# 2_bootleg-1-matrix.net
KiCad netlist of a schematic drawn in Altium Designer
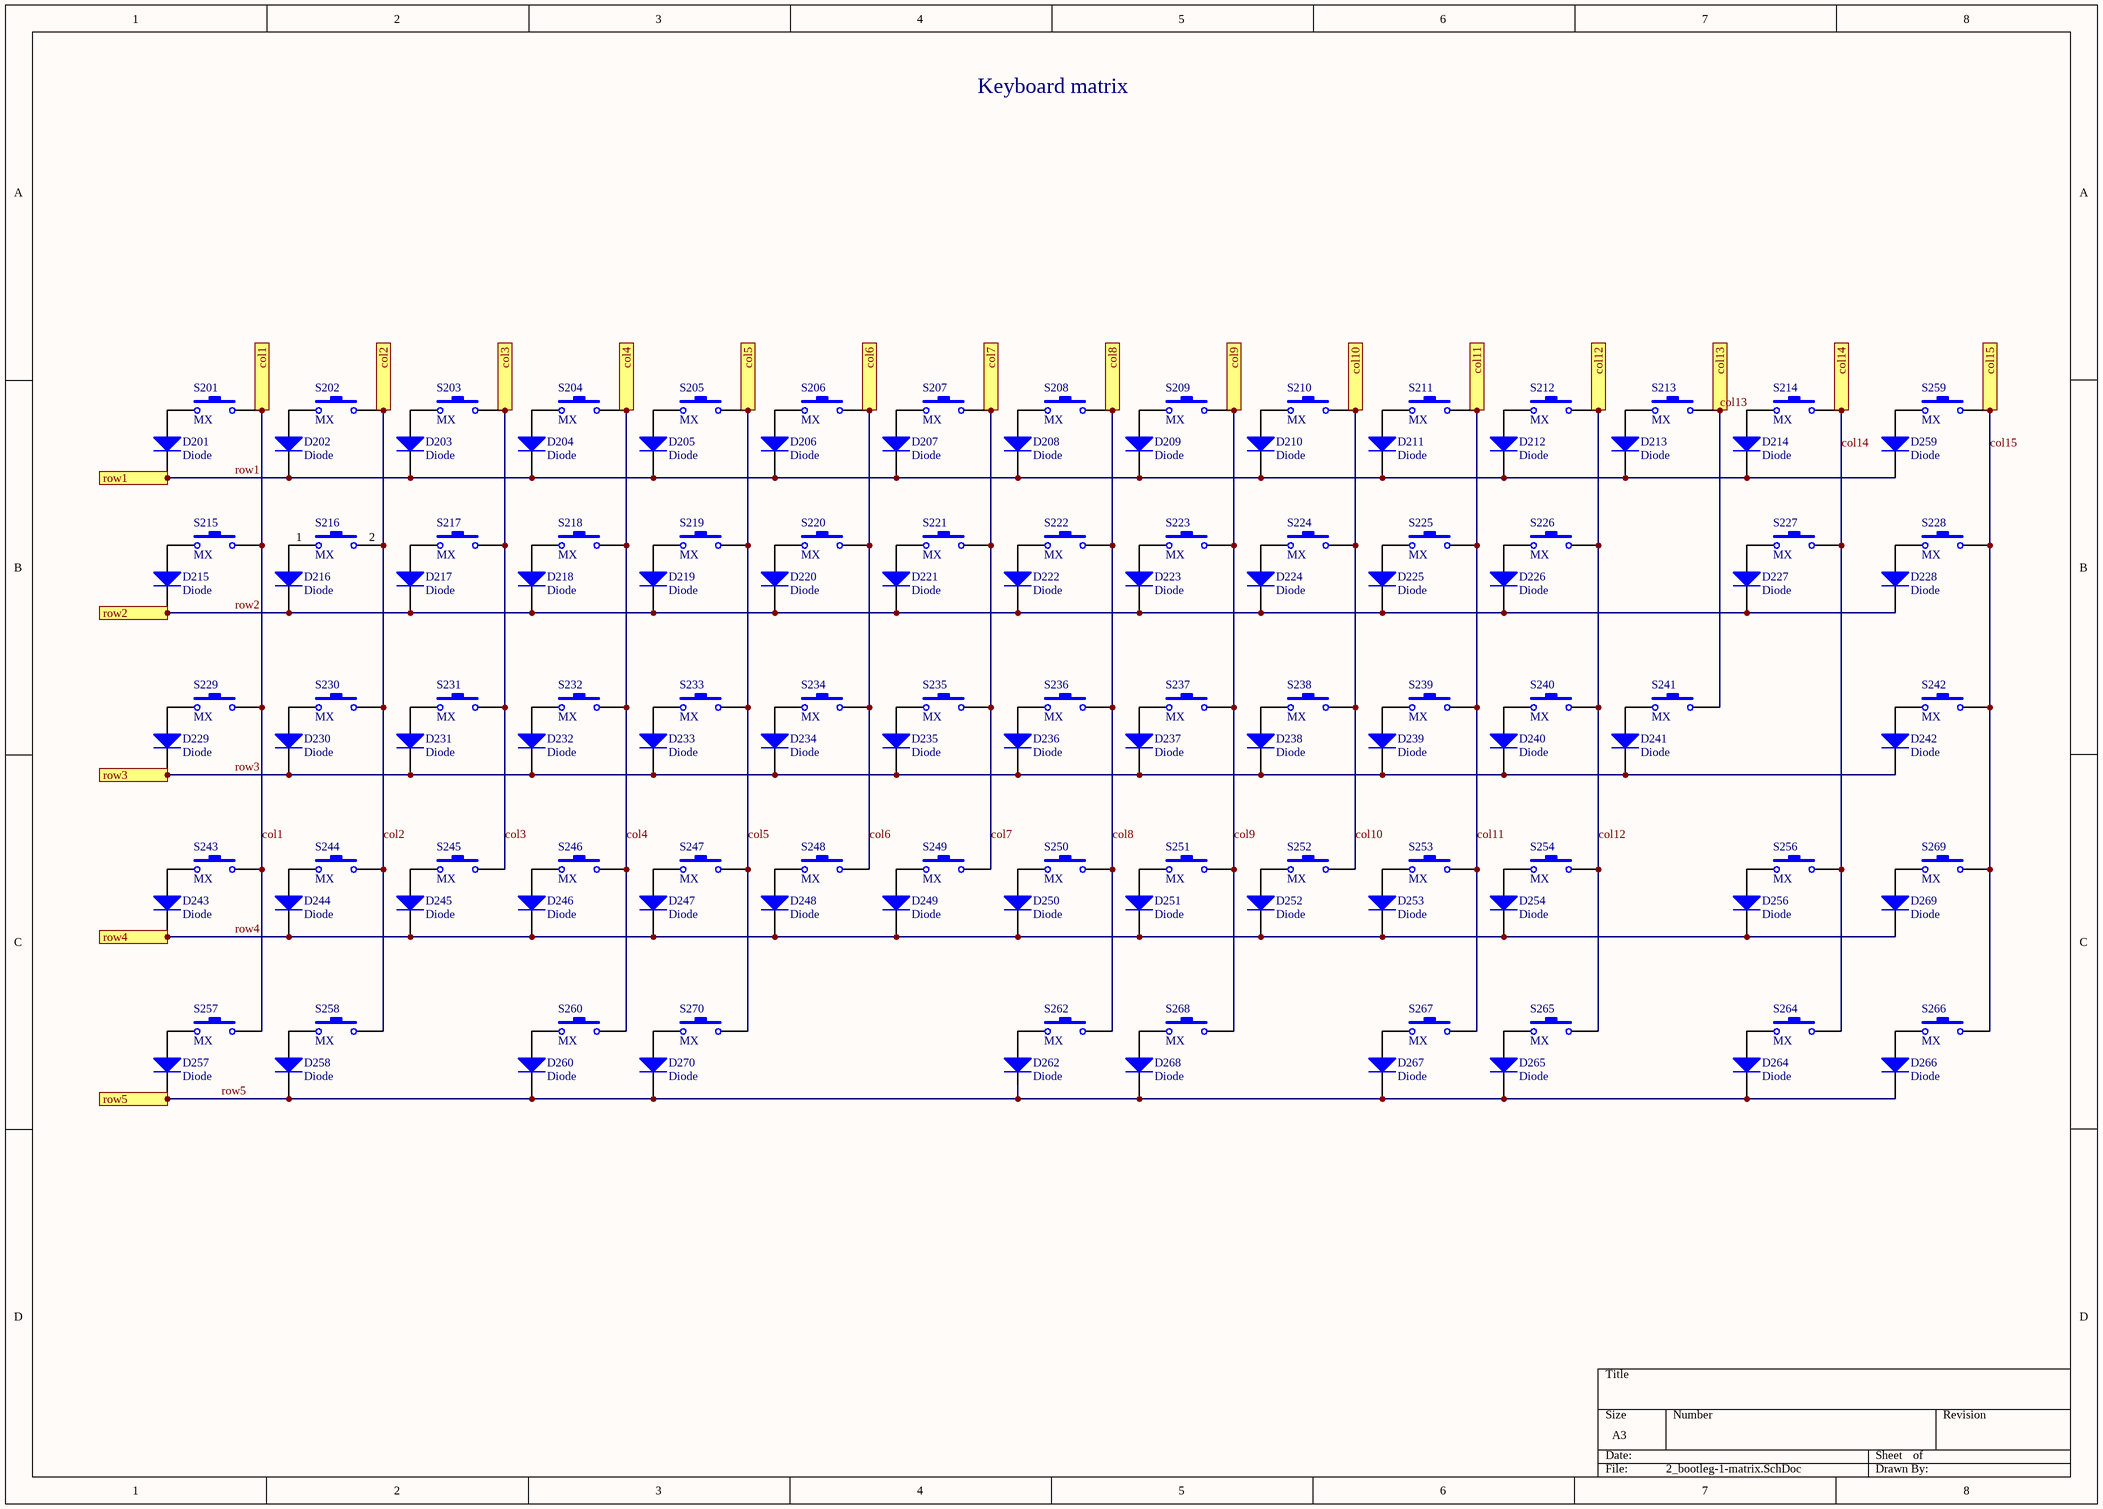
[diagram p0: 2_bootleg-1-matrix.SchDoc]

(export (version "E")
  (design (tool "Eeschema 10.0.6"))
  (components
    (comp (ref "D201")
      (value "Diode")
      (footprint "SOD-123")
      (description "Default Diode")
      (fields (field (name "MFG") "Bourns Inc.") (field (name "LCSC PART #") "C109002"))
      (libsource (lib "Miscellaneous Devices") (part "Diode"))
    )
    (comp (ref "D202")
      (value "Diode")
      (footprint "SOD-123")
      (description "Default Diode")
      (fields (field (name "MFG") "Bourns Inc.") (field (name "LCSC PART #") "C109002"))
      (libsource (lib "Miscellaneous Devices") (part "Diode"))
    )
    (comp (ref "D203")
      (value "Diode")
      (footprint "SOD-123")
      (description "Default Diode")
      (fields (field (name "MFG") "Bourns Inc.") (field (name "LCSC PART #") "C109002"))
      (libsource (lib "Miscellaneous Devices") (part "Diode"))
    )
    (comp (ref "D204")
      (value "Diode")
      (footprint "SOD-123")
      (description "Default Diode")
      (fields (field (name "MFG") "Bourns Inc.") (field (name "LCSC PART #") "C109002"))
      (libsource (lib "Miscellaneous Devices") (part "Diode"))
    )
    (comp (ref "D205")
      (value "Diode")
      (footprint "SOD-123")
      (description "Default Diode")
      (fields (field (name "MFG") "Bourns Inc.") (field (name "LCSC PART #") "C109002"))
      (libsource (lib "Miscellaneous Devices") (part "Diode"))
    )
    (comp (ref "D206")
      (value "Diode")
      (footprint "SOD-123")
      (description "Default Diode")
      (fields (field (name "MFG") "Bourns Inc.") (field (name "LCSC PART #") "C109002"))
      (libsource (lib "Miscellaneous Devices") (part "Diode"))
    )
    (comp (ref "D207")
      (value "Diode")
      (footprint "SOD-123")
      (description "Default Diode")
      (fields (field (name "MFG") "Bourns Inc.") (field (name "LCSC PART #") "C109002"))
      (libsource (lib "Miscellaneous Devices") (part "Diode"))
    )
    (comp (ref "D208")
      (value "Diode")
      (footprint "SOD-123")
      (description "Default Diode")
      (fields (field (name "MFG") "Bourns Inc.") (field (name "LCSC PART #") "C109002"))
      (libsource (lib "Miscellaneous Devices") (part "Diode"))
    )
    (comp (ref "D209")
      (value "Diode")
      (footprint "SOD-123")
      (description "Default Diode")
      (fields (field (name "MFG") "Bourns Inc.") (field (name "LCSC PART #") "C109002"))
      (libsource (lib "Miscellaneous Devices") (part "Diode"))
    )
    (comp (ref "D210")
      (value "Diode")
      (footprint "SOD-123")
      (description "Default Diode")
      (fields (field (name "MFG") "Bourns Inc.") (field (name "LCSC PART #") "C109002"))
      (libsource (lib "Miscellaneous Devices") (part "Diode"))
    )
    (comp (ref "D211")
      (value "Diode")
      (footprint "SOD-123")
      (description "Default Diode")
      (fields (field (name "MFG") "Bourns Inc.") (field (name "LCSC PART #") "C109002"))
      (libsource (lib "Miscellaneous Devices") (part "Diode"))
    )
    (comp (ref "D212")
      (value "Diode")
      (footprint "SOD-123")
      (description "Default Diode")
      (fields (field (name "MFG") "Bourns Inc.") (field (name "LCSC PART #") "C109002"))
      (libsource (lib "Miscellaneous Devices") (part "Diode"))
    )
    (comp (ref "D213")
      (value "Diode")
      (footprint "SOD-123")
      (description "Default Diode")
      (fields (field (name "MFG") "Bourns Inc.") (field (name "LCSC PART #") "C109002"))
      (libsource (lib "Miscellaneous Devices") (part "Diode"))
    )
    (comp (ref "D214")
      (value "Diode")
      (footprint "SOD-123")
      (description "Default Diode")
      (fields (field (name "MFG") "Bourns Inc.") (field (name "LCSC PART #") "C109002"))
      (libsource (lib "Miscellaneous Devices") (part "Diode"))
    )
    (comp (ref "D215")
      (value "Diode")
      (footprint "SOD-123")
      (description "Default Diode")
      (fields (field (name "MFG") "Bourns Inc.") (field (name "LCSC PART #") "C109002"))
      (libsource (lib "Miscellaneous Devices") (part "Diode"))
    )
    (comp (ref "D216")
      (value "Diode")
      (footprint "SOD-123")
      (description "Default Diode")
      (fields (field (name "MFG") "Bourns Inc.") (field (name "LCSC PART #") "C109002"))
      (libsource (lib "Miscellaneous Devices") (part "Diode"))
    )
    (comp (ref "D217")
      (value "Diode")
      (footprint "SOD-123")
      (description "Default Diode")
      (fields (field (name "MFG") "Bourns Inc.") (field (name "LCSC PART #") "C109002"))
      (libsource (lib "Miscellaneous Devices") (part "Diode"))
    )
    (comp (ref "D218")
      (value "Diode")
      (footprint "SOD-123")
      (description "Default Diode")
      (fields (field (name "MFG") "Bourns Inc.") (field (name "LCSC PART #") "C109002"))
      (libsource (lib "Miscellaneous Devices") (part "Diode"))
    )
    (comp (ref "D219")
      (value "Diode")
      (footprint "SOD-123")
      (description "Default Diode")
      (fields (field (name "MFG") "Bourns Inc.") (field (name "LCSC PART #") "C109002"))
      (libsource (lib "Miscellaneous Devices") (part "Diode"))
    )
    (comp (ref "D220")
      (value "Diode")
      (footprint "SOD-123")
      (description "Default Diode")
      (fields (field (name "MFG") "Bourns Inc.") (field (name "LCSC PART #") "C109002"))
      (libsource (lib "Miscellaneous Devices") (part "Diode"))
    )
    (comp (ref "D221")
      (value "Diode")
      (footprint "SOD-123")
      (description "Default Diode")
      (fields (field (name "MFG") "Bourns Inc.") (field (name "LCSC PART #") "C109002"))
      (libsource (lib "Miscellaneous Devices") (part "Diode"))
    )
    (comp (ref "D222")
      (value "Diode")
      (footprint "SOD-123")
      (description "Default Diode")
      (fields (field (name "MFG") "Bourns Inc.") (field (name "LCSC PART #") "C109002"))
      (libsource (lib "Miscellaneous Devices") (part "Diode"))
    )
    (comp (ref "D223")
      (value "Diode")
      (footprint "SOD-123")
      (description "Default Diode")
      (fields (field (name "MFG") "Bourns Inc.") (field (name "LCSC PART #") "C109002"))
      (libsource (lib "Miscellaneous Devices") (part "Diode"))
    )
    (comp (ref "D224")
      (value "Diode")
      (footprint "SOD-123")
      (description "Default Diode")
      (fields (field (name "MFG") "Bourns Inc.") (field (name "LCSC PART #") "C109002"))
      (libsource (lib "Miscellaneous Devices") (part "Diode"))
    )
    (comp (ref "D225")
      (value "Diode")
      (footprint "SOD-123")
      (description "Default Diode")
      (fields (field (name "MFG") "Bourns Inc.") (field (name "LCSC PART #") "C109002"))
      (libsource (lib "Miscellaneous Devices") (part "Diode"))
    )
    (comp (ref "D226")
      (value "Diode")
      (footprint "SOD-123")
      (description "Default Diode")
      (fields (field (name "MFG") "Bourns Inc.") (field (name "LCSC PART #") "C109002"))
      (libsource (lib "Miscellaneous Devices") (part "Diode"))
    )
    (comp (ref "D227")
      (value "Diode")
      (footprint "SOD-123")
      (description "Default Diode")
      (fields (field (name "MFG") "Bourns Inc.") (field (name "LCSC PART #") "C109002"))
      (libsource (lib "Miscellaneous Devices") (part "Diode"))
    )
    (comp (ref "D228")
      (value "Diode")
      (footprint "SOD-123")
      (description "Default Diode")
      (fields (field (name "MFG") "Bourns Inc.") (field (name "LCSC PART #") "C109002"))
      (libsource (lib "Miscellaneous Devices") (part "Diode"))
    )
    (comp (ref "D229")
      (value "Diode")
      (footprint "SOD-123")
      (description "Default Diode")
      (fields (field (name "MFG") "Bourns Inc.") (field (name "LCSC PART #") "C109002"))
      (libsource (lib "Miscellaneous Devices") (part "Diode"))
    )
    (comp (ref "D230")
      (value "Diode")
      (footprint "SOD-123")
      (description "Default Diode")
      (fields (field (name "MFG") "Bourns Inc.") (field (name "LCSC PART #") "C109002"))
      (libsource (lib "Miscellaneous Devices") (part "Diode"))
    )
    (comp (ref "D231")
      (value "Diode")
      (footprint "SOD-123")
      (description "Default Diode")
      (fields (field (name "MFG") "Bourns Inc.") (field (name "LCSC PART #") "C109002"))
      (libsource (lib "Miscellaneous Devices") (part "Diode"))
    )
    (comp (ref "D232")
      (value "Diode")
      (footprint "SOD-123")
      (description "Default Diode")
      (fields (field (name "MFG") "Bourns Inc.") (field (name "LCSC PART #") "C109002"))
      (libsource (lib "Miscellaneous Devices") (part "Diode"))
    )
    (comp (ref "D233")
      (value "Diode")
      (footprint "SOD-123")
      (description "Default Diode")
      (fields (field (name "MFG") "Bourns Inc.") (field (name "LCSC PART #") "C109002"))
      (libsource (lib "Miscellaneous Devices") (part "Diode"))
    )
    (comp (ref "D234")
      (value "Diode")
      (footprint "SOD-123")
      (description "Default Diode")
      (fields (field (name "MFG") "Bourns Inc.") (field (name "LCSC PART #") "C109002"))
      (libsource (lib "Miscellaneous Devices") (part "Diode"))
    )
    (comp (ref "D235")
      (value "Diode")
      (footprint "SOD-123")
      (description "Default Diode")
      (fields (field (name "MFG") "Bourns Inc.") (field (name "LCSC PART #") "C109002"))
      (libsource (lib "Miscellaneous Devices") (part "Diode"))
    )
    (comp (ref "D236")
      (value "Diode")
      (footprint "SOD-123")
      (description "Default Diode")
      (fields (field (name "MFG") "Bourns Inc.") (field (name "LCSC PART #") "C109002"))
      (libsource (lib "Miscellaneous Devices") (part "Diode"))
    )
    (comp (ref "D237")
      (value "Diode")
      (footprint "SOD-123")
      (description "Default Diode")
      (fields (field (name "MFG") "Bourns Inc.") (field (name "LCSC PART #") "C109002"))
      (libsource (lib "Miscellaneous Devices") (part "Diode"))
    )
    (comp (ref "D238")
      (value "Diode")
      (footprint "SOD-123")
      (description "Default Diode")
      (fields (field (name "MFG") "Bourns Inc.") (field (name "LCSC PART #") "C109002"))
      (libsource (lib "Miscellaneous Devices") (part "Diode"))
    )
    (comp (ref "D239")
      (value "Diode")
      (footprint "SOD-123")
      (description "Default Diode")
      (fields (field (name "MFG") "Bourns Inc.") (field (name "LCSC PART #") "C109002"))
      (libsource (lib "Miscellaneous Devices") (part "Diode"))
    )
    (comp (ref "D240")
      (value "Diode")
      (footprint "SOD-123")
      (description "Default Diode")
      (fields (field (name "MFG") "Bourns Inc.") (field (name "LCSC PART #") "C109002"))
      (libsource (lib "Miscellaneous Devices") (part "Diode"))
    )
    (comp (ref "D241")
      (value "Diode")
      (footprint "SOD-123")
      (description "Default Diode")
      (fields (field (name "MFG") "Bourns Inc.") (field (name "LCSC PART #") "C109002"))
      (libsource (lib "Miscellaneous Devices") (part "Diode"))
    )
    (comp (ref "D242")
      (value "Diode")
      (footprint "SOD-123")
      (description "Default Diode")
      (fields (field (name "MFG") "Bourns Inc.") (field (name "LCSC PART #") "C109002"))
      (libsource (lib "Miscellaneous Devices") (part "Diode"))
    )
    (comp (ref "D243")
      (value "Diode")
      (footprint "SOD-123")
      (description "Default Diode")
      (fields (field (name "MFG") "Bourns Inc.") (field (name "LCSC PART #") "C109002"))
      (libsource (lib "Miscellaneous Devices") (part "Diode"))
    )
    (comp (ref "D244")
      (value "Diode")
      (footprint "SOD-123")
      (description "Default Diode")
      (fields (field (name "MFG") "Bourns Inc.") (field (name "LCSC PART #") "C109002"))
      (libsource (lib "Miscellaneous Devices") (part "Diode"))
    )
    (comp (ref "D245")
      (value "Diode")
      (footprint "SOD-123")
      (description "Default Diode")
      (fields (field (name "MFG") "Bourns Inc.") (field (name "LCSC PART #") "C109002"))
      (libsource (lib "Miscellaneous Devices") (part "Diode"))
    )
    (comp (ref "D246")
      (value "Diode")
      (footprint "SOD-123")
      (description "Default Diode")
      (fields (field (name "MFG") "Bourns Inc.") (field (name "LCSC PART #") "C109002"))
      (libsource (lib "Miscellaneous Devices") (part "Diode"))
    )
    (comp (ref "D247")
      (value "Diode")
      (footprint "SOD-123")
      (description "Default Diode")
      (fields (field (name "MFG") "Bourns Inc.") (field (name "LCSC PART #") "C109002"))
      (libsource (lib "Miscellaneous Devices") (part "Diode"))
    )
    (comp (ref "D248")
      (value "Diode")
      (footprint "SOD-123")
      (description "Default Diode")
      (fields (field (name "MFG") "Bourns Inc.") (field (name "LCSC PART #") "C109002"))
      (libsource (lib "Miscellaneous Devices") (part "Diode"))
    )
    (comp (ref "D249")
      (value "Diode")
      (footprint "SOD-123")
      (description "Default Diode")
      (fields (field (name "MFG") "Bourns Inc.") (field (name "LCSC PART #") "C109002"))
      (libsource (lib "Miscellaneous Devices") (part "Diode"))
    )
    (comp (ref "D250")
      (value "Diode")
      (footprint "SOD-123")
      (description "Default Diode")
      (fields (field (name "MFG") "Bourns Inc.") (field (name "LCSC PART #") "C109002"))
      (libsource (lib "Miscellaneous Devices") (part "Diode"))
    )
    (comp (ref "D251")
      (value "Diode")
      (footprint "SOD-123")
      (description "Default Diode")
      (fields (field (name "MFG") "Bourns Inc.") (field (name "LCSC PART #") "C109002"))
      (libsource (lib "Miscellaneous Devices") (part "Diode"))
    )
    (comp (ref "D252")
      (value "Diode")
      (footprint "SOD-123")
      (description "Default Diode")
      (fields (field (name "MFG") "Bourns Inc.") (field (name "LCSC PART #") "C109002"))
      (libsource (lib "Miscellaneous Devices") (part "Diode"))
    )
    (comp (ref "D253")
      (value "Diode")
      (footprint "SOD-123")
      (description "Default Diode")
      (fields (field (name "MFG") "Bourns Inc.") (field (name "LCSC PART #") "C109002"))
      (libsource (lib "Miscellaneous Devices") (part "Diode"))
    )
    (comp (ref "D254")
      (value "Diode")
      (footprint "SOD-123")
      (description "Default Diode")
      (fields (field (name "MFG") "Bourns Inc.") (field (name "LCSC PART #") "C109002"))
      (libsource (lib "Miscellaneous Devices") (part "Diode"))
    )
    (comp (ref "D256")
      (value "Diode")
      (footprint "SOD-123")
      (description "Default Diode")
      (fields (field (name "MFG") "Bourns Inc.") (field (name "LCSC PART #") "C109002"))
      (libsource (lib "Miscellaneous Devices") (part "Diode"))
    )
    (comp (ref "D257")
      (value "Diode")
      (footprint "SOD-123")
      (description "Default Diode")
      (fields (field (name "MFG") "Bourns Inc.") (field (name "LCSC PART #") "C109002"))
      (libsource (lib "Miscellaneous Devices") (part "Diode"))
    )
    (comp (ref "D258")
      (value "Diode")
      (footprint "SOD-123")
      (description "Default Diode")
      (fields (field (name "MFG") "Bourns Inc.") (field (name "LCSC PART #") "C109002"))
      (libsource (lib "Miscellaneous Devices") (part "Diode"))
    )
    (comp (ref "D259")
      (value "Diode")
      (footprint "SOD-123")
      (description "Default Diode")
      (fields (field (name "MFG") "Bourns Inc.") (field (name "LCSC PART #") "C109002"))
      (libsource (lib "Miscellaneous Devices") (part "Diode"))
    )
    (comp (ref "D260")
      (value "Diode")
      (footprint "SOD-123")
      (description "Default Diode")
      (fields (field (name "MFG") "Bourns Inc.") (field (name "LCSC PART #") "C109002"))
      (libsource (lib "Miscellaneous Devices") (part "Diode"))
    )
    (comp (ref "D262")
      (value "Diode")
      (footprint "SOD-123")
      (description "Default Diode")
      (fields (field (name "MFG") "Bourns Inc.") (field (name "LCSC PART #") "C109002"))
      (libsource (lib "Miscellaneous Devices") (part "Diode"))
    )
    (comp (ref "D264")
      (value "Diode")
      (footprint "SOD-123")
      (description "Default Diode")
      (fields (field (name "MFG") "Bourns Inc.") (field (name "LCSC PART #") "C109002"))
      (libsource (lib "Miscellaneous Devices") (part "Diode"))
    )
    (comp (ref "D265")
      (value "Diode")
      (footprint "SOD-123")
      (description "Default Diode")
      (fields (field (name "MFG") "Bourns Inc.") (field (name "LCSC PART #") "C109002"))
      (libsource (lib "Miscellaneous Devices") (part "Diode"))
    )
    (comp (ref "D266")
      (value "Diode")
      (footprint "SOD-123")
      (description "Default Diode")
      (fields (field (name "MFG") "Bourns Inc.") (field (name "LCSC PART #") "C109002"))
      (libsource (lib "Miscellaneous Devices") (part "Diode"))
    )
    (comp (ref "D267")
      (value "Diode")
      (footprint "SOD-123")
      (description "Default Diode")
      (fields (field (name "MFG") "Bourns Inc.") (field (name "LCSC PART #") "C109002"))
      (libsource (lib "Miscellaneous Devices") (part "Diode"))
    )
    (comp (ref "D268")
      (value "Diode")
      (footprint "SOD-123")
      (description "Default Diode")
      (fields (field (name "MFG") "Bourns Inc.") (field (name "LCSC PART #") "C109002"))
      (libsource (lib "Miscellaneous Devices") (part "Diode"))
    )
    (comp (ref "D269")
      (value "Diode")
      (footprint "SOD-123")
      (description "Default Diode")
      (fields (field (name "MFG") "Bourns Inc.") (field (name "LCSC PART #") "C109002"))
      (libsource (lib "Miscellaneous Devices") (part "Diode"))
    )
    (comp (ref "D270")
      (value "Diode")
      (footprint "SOD-123")
      (description "Default Diode")
      (fields (field (name "MFG") "Bourns Inc.") (field (name "LCSC PART #") "C109002"))
      (libsource (lib "Miscellaneous Devices") (part "Diode"))
    )
    (comp (ref "S201")
      (value "MX")
      (footprint "MX-switch - switched pol")
      (description "Switch")
      (libsource (lib "Miscellaneous Devices") (part "SW-PB"))
    )
    (comp (ref "S202")
      (value "MX")
      (footprint "MX-switch - switched pol - connector")
      (description "Switch")
      (libsource (lib "Miscellaneous Devices") (part "SW-PB"))
    )
    (comp (ref "S203")
      (value "MX")
      (footprint "MX-switch - switched pol")
      (description "Switch")
      (libsource (lib "Miscellaneous Devices") (part "SW-PB"))
    )
    (comp (ref "S204")
      (value "MX")
      (footprint "MX-switch - switched pol")
      (description "Switch")
      (libsource (lib "Miscellaneous Devices") (part "SW-PB"))
    )
    (comp (ref "S205")
      (value "MX")
      (footprint "MX-switch - switched pol")
      (description "Switch")
      (libsource (lib "Miscellaneous Devices") (part "SW-PB"))
    )
    (comp (ref "S206")
      (value "MX")
      (footprint "MX-switch - switched pol")
      (description "Switch")
      (libsource (lib "Miscellaneous Devices") (part "SW-PB"))
    )
    (comp (ref "S207")
      (value "MX")
      (footprint "MX-switch - switched pol")
      (description "Switch")
      (libsource (lib "Miscellaneous Devices") (part "SW-PB"))
    )
    (comp (ref "S208")
      (value "MX")
      (footprint "MX-switch - switched pol")
      (description "Switch")
      (libsource (lib "Miscellaneous Devices") (part "SW-PB"))
    )
    (comp (ref "S209")
      (value "MX")
      (footprint "MX-switch - switched pol")
      (description "Switch")
      (libsource (lib "Miscellaneous Devices") (part "SW-PB"))
    )
    (comp (ref "S210")
      (value "MX")
      (footprint "MX-switch - switched pol")
      (description "Switch")
      (libsource (lib "Miscellaneous Devices") (part "SW-PB"))
    )
    (comp (ref "S211")
      (value "MX")
      (footprint "MX-switch - switched pol")
      (description "Switch")
      (libsource (lib "Miscellaneous Devices") (part "SW-PB"))
    )
    (comp (ref "S212")
      (value "MX")
      (footprint "MX-switch - switched pol")
      (description "Switch")
      (libsource (lib "Miscellaneous Devices") (part "SW-PB"))
    )
    (comp (ref "S213")
      (value "MX")
      (footprint "MX-switch - switched pol")
      (description "Switch")
      (libsource (lib "Miscellaneous Devices") (part "SW-PB"))
    )
    (comp (ref "S214")
      (value "MX")
      (footprint "MX-switch - switched pol")
      (description "Switch")
      (libsource (lib "Miscellaneous Devices") (part "SW-PB"))
    )
    (comp (ref "S215")
      (value "MX")
      (footprint "MX-switch - 1.5U")
      (description "TAB")
      (libsource (lib "Miscellaneous Devices") (part "SW-PB"))
    )
    (comp (ref "S216")
      (value "MX")
      (footprint "MX-switch - switched pol")
      (description "Switch")
      (libsource (lib "") (part "SW-PB_1"))
    )
    (comp (ref "S217")
      (value "MX")
      (footprint "MX-switch - switched pol")
      (description "Switch")
      (libsource (lib "Miscellaneous Devices") (part "SW-PB"))
    )
    (comp (ref "S218")
      (value "MX")
      (footprint "MX-switch - switched pol")
      (description "Switch")
      (libsource (lib "Miscellaneous Devices") (part "SW-PB"))
    )
    (comp (ref "S219")
      (value "MX")
      (footprint "MX-switch - switched pol")
      (description "Switch")
      (libsource (lib "Miscellaneous Devices") (part "SW-PB"))
    )
    (comp (ref "S220")
      (value "MX")
      (footprint "MX-switch - switched pol")
      (description "Switch")
      (libsource (lib "Miscellaneous Devices") (part "SW-PB"))
    )
    (comp (ref "S221")
      (value "MX")
      (footprint "MX-switch - switched pol")
      (description "Switch")
      (libsource (lib "Miscellaneous Devices") (part "SW-PB"))
    )
    (comp (ref "S222")
      (value "MX")
      (footprint "MX-switch - switched pol")
      (description "Switch")
      (libsource (lib "Miscellaneous Devices") (part "SW-PB"))
    )
    (comp (ref "S223")
      (value "MX")
      (footprint "MX-switch - switched pol")
      (description "Switch")
      (libsource (lib "Miscellaneous Devices") (part "SW-PB"))
    )
    (comp (ref "S224")
      (value "MX")
      (footprint "MX-switch - switched pol")
      (description "Switch")
      (libsource (lib "Miscellaneous Devices") (part "SW-PB"))
    )
    (comp (ref "S225")
      (value "MX")
      (footprint "MX-switch - switched pol")
      (description "Switch")
      (libsource (lib "Miscellaneous Devices") (part "SW-PB"))
    )
    (comp (ref "S226")
      (value "MX")
      (footprint "MX-switch")
      (description "Switch")
      (libsource (lib "Miscellaneous Devices") (part "SW-PB"))
    )
    (comp (ref "S227")
      (value "MX")
      (footprint "MX-switch - switched pol")
      (description "Switch")
      (libsource (lib "Miscellaneous Devices") (part "SW-PB"))
    )
    (comp (ref "S228")
      (value "MX")
      (footprint "MX-switch - 1.5U")
      (description "Switch")
      (libsource (lib "Miscellaneous Devices") (part "SW-PB"))
    )
    (comp (ref "S229")
      (value "MX")
      (footprint "MX-switch - CAPS")
      (description "Switch")
      (libsource (lib "Miscellaneous Devices") (part "SW-PB"))
    )
    (comp (ref "S230")
      (value "MX")
      (footprint "MX-switch - switched pol")
      (description "Switch")
      (libsource (lib "Miscellaneous Devices") (part "SW-PB"))
    )
    (comp (ref "S231")
      (value "MX")
      (footprint "MX-switch - switched pol")
      (description "Switch")
      (libsource (lib "Miscellaneous Devices") (part "SW-PB"))
    )
    (comp (ref "S232")
      (value "MX")
      (footprint "MX-switch - switched pol")
      (description "Switch")
      (libsource (lib "Miscellaneous Devices") (part "SW-PB"))
    )
    (comp (ref "S233")
      (value "MX")
      (footprint "MX-switch - switched pol")
      (description "Switch")
      (libsource (lib "Miscellaneous Devices") (part "SW-PB"))
    )
    (comp (ref "S234")
      (value "MX")
      (footprint "MX-switch - switched pol")
      (description "Switch")
      (libsource (lib "Miscellaneous Devices") (part "SW-PB"))
    )
    (comp (ref "S235")
      (value "MX")
      (footprint "MX-switch - switched pol")
      (description "Switch")
      (libsource (lib "Miscellaneous Devices") (part "SW-PB"))
    )
    (comp (ref "S236")
      (value "MX")
      (footprint "MX-switch - switched pol")
      (description "Switch")
      (libsource (lib "Miscellaneous Devices") (part "SW-PB"))
    )
    (comp (ref "S237")
      (value "MX")
      (footprint "MX-switch - switched pol")
      (description "Switch")
      (libsource (lib "Miscellaneous Devices") (part "SW-PB"))
    )
    (comp (ref "S238")
      (value "MX")
      (footprint "MX-switch - switched pol")
      (description "Switch")
      (libsource (lib "Miscellaneous Devices") (part "SW-PB"))
    )
    (comp (ref "S239")
      (value "MX")
      (footprint "MX-switch")
      (description "Switch")
      (libsource (lib "Miscellaneous Devices") (part "SW-PB"))
    )
    (comp (ref "S240")
      (value "MX")
      (footprint "MX-switch - switched pol")
      (description "Switch")
      (libsource (lib "Miscellaneous Devices") (part "SW-PB"))
    )
    (comp (ref "S241")
      (value "MX")
      (footprint "MX-switch")
      (description "Switch")
      (libsource (lib "Miscellaneous Devices") (part "SW-PB"))
    )
    (comp (ref "S242")
      (value "MX")
      (footprint "MX-switch - Enter")
      (description "Switch")
      (libsource (lib "Miscellaneous Devices") (part "SW-PB"))
    )
    (comp (ref "S243")
      (value "MX")
      (footprint "MX-switch - Left shift")
      (description "Switch")
      (libsource (lib "Miscellaneous Devices") (part "SW-PB"))
    )
    (comp (ref "S244")
      (value "MX")
      (footprint "MX-switch")
      (description "Switch")
      (libsource (lib "Miscellaneous Devices") (part "SW-PB"))
    )
    (comp (ref "S245")
      (value "MX")
      (footprint "MX-switch - switched pol")
      (description "Switch")
      (libsource (lib "Miscellaneous Devices") (part "SW-PB"))
    )
    (comp (ref "S246")
      (value "MX")
      (footprint "MX-switch - switched pol")
      (description "Switch")
      (libsource (lib "Miscellaneous Devices") (part "SW-PB"))
    )
    (comp (ref "S247")
      (value "MX")
      (footprint "MX-switch - switched pol")
      (description "Switch")
      (libsource (lib "Miscellaneous Devices") (part "SW-PB"))
    )
    (comp (ref "S248")
      (value "MX")
      (footprint "MX-switch - switched pol")
      (description "Switch")
      (libsource (lib "Miscellaneous Devices") (part "SW-PB"))
    )
    (comp (ref "S249")
      (value "MX")
      (footprint "MX-switch - switched pol")
      (description "Switch")
      (libsource (lib "Miscellaneous Devices") (part "SW-PB"))
    )
    (comp (ref "S250")
      (value "MX")
      (footprint "MX-switch - switched pol")
      (description "Switch")
      (libsource (lib "Miscellaneous Devices") (part "SW-PB"))
    )
    (comp (ref "S251")
      (value "MX")
      (footprint "MX-switch - switched pol")
      (description "Switch")
      (libsource (lib "Miscellaneous Devices") (part "SW-PB"))
    )
    (comp (ref "S252")
      (value "MX")
      (footprint "MX-switch - switched pol")
      (description "Switch")
      (libsource (lib "Miscellaneous Devices") (part "SW-PB"))
    )
    (comp (ref "S253")
      (value "MX")
      (footprint "MX-switch - switched pol")
      (description "Switch")
      (libsource (lib "Miscellaneous Devices") (part "SW-PB"))
    )
    (comp (ref "S254")
      (value "MX")
      (footprint "MX-switch - switched pol")
      (description "Switch")
      (libsource (lib "Miscellaneous Devices") (part "SW-PB"))
    )
    (comp (ref "S256")
      (value "MX")
      (footprint "MX-switch - right shift")
      (description "Switch")
      (libsource (lib "Miscellaneous Devices") (part "SW-PB"))
    )
    (comp (ref "S257")
      (value "MX")
      (footprint "MX-switch - 1.5u MOD-L")
      (description "Switch")
      (libsource (lib "Miscellaneous Devices") (part "SW-PB"))
    )
    (comp (ref "S258")
      (value "MX")
      (footprint "MX-switch - 1u MOD-L")
      (description "Switch")
      (libsource (lib "Miscellaneous Devices") (part "SW-PB"))
    )
    (comp (ref "S259")
      (value "MX")
      (footprint "MX-switch - backspace")
      (description "Switch")
      (libsource (lib "Miscellaneous Devices") (part "SW-PB"))
    )
    (comp (ref "S260")
      (value "MX")
      (footprint "MX-switch - 1.5u MOD-L")
      (description "Switch")
      (libsource (lib "Miscellaneous Devices") (part "SW-PB"))
    )
    (comp (ref "S262")
      (value "MX")
      (footprint "MX-switch - Space_V3")
      (description "Switch")
      (libsource (lib "Miscellaneous Devices") (part "SW-PB"))
    )
    (comp (ref "S264")
      (value "MX")
      (footprint "MX-switch - 1u MOD-R")
      (description "Switch")
      (libsource (lib "Miscellaneous Devices") (part "SW-PB"))
    )
    (comp (ref "S265")
      (value "MX")
      (footprint "MX-switch - 1.5u MOD-R")
      (description "Switch")
      (libsource (lib "Miscellaneous Devices") (part "SW-PB"))
    )
    (comp (ref "S266")
      (value "MX")
      (footprint "MX-switch - 1.5u MOD-R")
      (description "Switch")
      (libsource (lib "Miscellaneous Devices") (part "SW-PB"))
    )
    (comp (ref "S267")
      (value "MX")
      (footprint "MX-switch")
      (description "Switch")
      (libsource (lib "Miscellaneous Devices") (part "SW-PB"))
    )
    (comp (ref "S268")
      (value "MX")
      (footprint "MX-switch - R split space_V2")
      (description "Switch")
      (libsource (lib "Miscellaneous Devices") (part "SW-PB"))
    )
    (comp (ref "S269")
      (value "MX")
      (footprint "MX-switch")
      (description "Switch")
      (libsource (lib "Miscellaneous Devices") (part "SW-PB"))
    )
    (comp (ref "S270")
      (value "MX")
      (footprint "MX-switch - L split space_V2")
      (description "Switch")
      (libsource (lib "Miscellaneous Devices") (part "SW-PB"))
    )
  )
  (nets
    (net (code "1") (name "/col1") (class "Default")
      (node (ref "S201") (pin "2") (pinfunction "2_2") (pintype "passive"))
      (node (ref "S215") (pin "2") (pinfunction "2_2") (pintype "passive"))
      (node (ref "S229") (pin "2") (pinfunction "2_2") (pintype "passive"))
      (node (ref "S243") (pin "2") (pinfunction "2_2") (pintype "passive"))
      (node (ref "S257") (pin "1") (pinfunction "1_1") (pintype "passive"))
    )
    (net (code "2") (name "/col2") (class "Default")
      (node (ref "S202") (pin "2") (pinfunction "2_2") (pintype "passive"))
      (node (ref "S216") (pin "2") (pinfunction "2_2") (pintype "passive"))
      (node (ref "S230") (pin "2") (pinfunction "2_2") (pintype "passive"))
      (node (ref "S244") (pin "2") (pinfunction "2_2") (pintype "passive"))
      (node (ref "S258") (pin "2") (pinfunction "2_2") (pintype "passive"))
    )
    (net (code "3") (name "/col3") (class "Default")
      (node (ref "S203") (pin "2") (pinfunction "2_2") (pintype "passive"))
      (node (ref "S217") (pin "2") (pinfunction "2_2") (pintype "passive"))
      (node (ref "S231") (pin "2") (pinfunction "2_2") (pintype "passive"))
      (node (ref "S245") (pin "2") (pinfunction "2_2") (pintype "passive"))
    )
    (net (code "4") (name "/col4") (class "Default")
      (node (ref "S204") (pin "2") (pinfunction "2_2") (pintype "passive"))
      (node (ref "S218") (pin "2") (pinfunction "2_2") (pintype "passive"))
      (node (ref "S232") (pin "2") (pinfunction "2_2") (pintype "passive"))
      (node (ref "S246") (pin "2") (pinfunction "2_2") (pintype "passive"))
      (node (ref "S260") (pin "2") (pinfunction "2_2") (pintype "passive"))
    )
    (net (code "5") (name "/col5") (class "Default")
      (node (ref "S205") (pin "2") (pinfunction "2_2") (pintype "passive"))
      (node (ref "S219") (pin "2") (pinfunction "2_2") (pintype "passive"))
      (node (ref "S233") (pin "2") (pinfunction "2_2") (pintype "passive"))
      (node (ref "S247") (pin "2") (pinfunction "2_2") (pintype "passive"))
      (node (ref "S270") (pin "2") (pinfunction "2_2") (pintype "passive"))
    )
    (net (code "6") (name "/col6") (class "Default")
      (node (ref "S206") (pin "2") (pinfunction "2_2") (pintype "passive"))
      (node (ref "S220") (pin "2") (pinfunction "2_2") (pintype "passive"))
      (node (ref "S234") (pin "2") (pinfunction "2_2") (pintype "passive"))
      (node (ref "S248") (pin "2") (pinfunction "2_2") (pintype "passive"))
    )
    (net (code "7") (name "/col7") (class "Default")
      (node (ref "S207") (pin "2") (pinfunction "2_2") (pintype "passive"))
      (node (ref "S221") (pin "2") (pinfunction "2_2") (pintype "passive"))
      (node (ref "S235") (pin "2") (pinfunction "2_2") (pintype "passive"))
      (node (ref "S249") (pin "2") (pinfunction "2_2") (pintype "passive"))
    )
    (net (code "8") (name "/col8") (class "Default")
      (node (ref "S208") (pin "2") (pinfunction "2_2") (pintype "passive"))
      (node (ref "S222") (pin "2") (pinfunction "2_2") (pintype "passive"))
      (node (ref "S236") (pin "2") (pinfunction "2_2") (pintype "passive"))
      (node (ref "S250") (pin "2") (pinfunction "2_2") (pintype "passive"))
      (node (ref "S262") (pin "2") (pinfunction "2_2") (pintype "passive"))
    )
    (net (code "9") (name "/col9") (class "Default")
      (node (ref "S209") (pin "2") (pinfunction "2_2") (pintype "passive"))
      (node (ref "S223") (pin "2") (pinfunction "2_2") (pintype "passive"))
      (node (ref "S237") (pin "2") (pinfunction "2_2") (pintype "passive"))
      (node (ref "S251") (pin "2") (pinfunction "2_2") (pintype "passive"))
      (node (ref "S268") (pin "2") (pinfunction "2_2") (pintype "passive"))
    )
    (net (code "10") (name "/col10") (class "Default")
      (node (ref "S210") (pin "2") (pinfunction "2_2") (pintype "passive"))
      (node (ref "S224") (pin "2") (pinfunction "2_2") (pintype "passive"))
      (node (ref "S238") (pin "2") (pinfunction "2_2") (pintype "passive"))
      (node (ref "S252") (pin "2") (pinfunction "2_2") (pintype "passive"))
    )
    (net (code "11") (name "/col11") (class "Default")
      (node (ref "S211") (pin "2") (pinfunction "2_2") (pintype "passive"))
      (node (ref "S225") (pin "2") (pinfunction "2_2") (pintype "passive"))
      (node (ref "S239") (pin "2") (pinfunction "2_2") (pintype "passive"))
      (node (ref "S253") (pin "2") (pinfunction "2_2") (pintype "passive"))
      (node (ref "S267") (pin "2") (pinfunction "2_2") (pintype "passive"))
    )
    (net (code "12") (name "/col12") (class "Default")
      (node (ref "S212") (pin "2") (pinfunction "2_2") (pintype "passive"))
      (node (ref "S226") (pin "2") (pinfunction "2_2") (pintype "passive"))
      (node (ref "S240") (pin "2") (pinfunction "2_2") (pintype "passive"))
      (node (ref "S254") (pin "2") (pinfunction "2_2") (pintype "passive"))
      (node (ref "S265") (pin "1") (pinfunction "1_1") (pintype "passive"))
    )
    (net (code "13") (name "/col13") (class "Default")
      (node (ref "S213") (pin "2") (pinfunction "2_2") (pintype "passive"))
      (node (ref "S241") (pin "2") (pinfunction "2_2") (pintype "passive"))
    )
    (net (code "14") (name "/col14") (class "Default")
      (node (ref "S214") (pin "2") (pinfunction "2_2") (pintype "passive"))
      (node (ref "S227") (pin "2") (pinfunction "2_2") (pintype "passive"))
      (node (ref "S256") (pin "2") (pinfunction "2_2") (pintype "passive"))
      (node (ref "S264") (pin "2") (pinfunction "2_2") (pintype "passive"))
    )
    (net (code "15") (name "/col15") (class "Default")
      (node (ref "S228") (pin "2") (pinfunction "2_2") (pintype "passive"))
      (node (ref "S242") (pin "2") (pinfunction "2_2") (pintype "passive"))
      (node (ref "S259") (pin "2") (pinfunction "2_2") (pintype "passive"))
      (node (ref "S266") (pin "2") (pinfunction "2_2") (pintype "passive"))
      (node (ref "S269") (pin "2") (pinfunction "2_2") (pintype "passive"))
    )
    (net (code "16") (name "/row1") (class "Default")
      (node (ref "D201") (pin "2") (pinfunction "K_2") (pintype "passive"))
      (node (ref "D202") (pin "2") (pinfunction "K_2") (pintype "passive"))
      (node (ref "D203") (pin "2") (pinfunction "K_2") (pintype "passive"))
      (node (ref "D204") (pin "2") (pinfunction "K_2") (pintype "passive"))
      (node (ref "D205") (pin "2") (pinfunction "K_2") (pintype "passive"))
      (node (ref "D206") (pin "2") (pinfunction "K_2") (pintype "passive"))
      (node (ref "D207") (pin "2") (pinfunction "K_2") (pintype "passive"))
      (node (ref "D208") (pin "2") (pinfunction "K_2") (pintype "passive"))
      (node (ref "D209") (pin "2") (pinfunction "K_2") (pintype "passive"))
      (node (ref "D210") (pin "2") (pinfunction "K_2") (pintype "passive"))
      (node (ref "D211") (pin "2") (pinfunction "K_2") (pintype "passive"))
      (node (ref "D212") (pin "2") (pinfunction "K_2") (pintype "passive"))
      (node (ref "D213") (pin "2") (pinfunction "K_2") (pintype "passive"))
      (node (ref "D214") (pin "2") (pinfunction "K_2") (pintype "passive"))
      (node (ref "D259") (pin "2") (pinfunction "K_2") (pintype "passive"))
    )
    (net (code "17") (name "/row2") (class "Default")
      (node (ref "D215") (pin "2") (pinfunction "K_2") (pintype "passive"))
      (node (ref "D216") (pin "2") (pinfunction "K_2") (pintype "passive"))
      (node (ref "D217") (pin "2") (pinfunction "K_2") (pintype "passive"))
      (node (ref "D218") (pin "2") (pinfunction "K_2") (pintype "passive"))
      (node (ref "D219") (pin "2") (pinfunction "K_2") (pintype "passive"))
      (node (ref "D220") (pin "2") (pinfunction "K_2") (pintype "passive"))
      (node (ref "D221") (pin "2") (pinfunction "K_2") (pintype "passive"))
      (node (ref "D222") (pin "2") (pinfunction "K_2") (pintype "passive"))
      (node (ref "D223") (pin "2") (pinfunction "K_2") (pintype "passive"))
      (node (ref "D224") (pin "2") (pinfunction "K_2") (pintype "passive"))
      (node (ref "D225") (pin "2") (pinfunction "K_2") (pintype "passive"))
      (node (ref "D226") (pin "2") (pinfunction "K_2") (pintype "passive"))
      (node (ref "D227") (pin "2") (pinfunction "K_2") (pintype "passive"))
      (node (ref "D228") (pin "2") (pinfunction "K_2") (pintype "passive"))
    )
    (net (code "18") (name "/row3") (class "Default")
      (node (ref "D229") (pin "2") (pinfunction "K_2") (pintype "passive"))
      (node (ref "D230") (pin "2") (pinfunction "K_2") (pintype "passive"))
      (node (ref "D231") (pin "2") (pinfunction "K_2") (pintype "passive"))
      (node (ref "D232") (pin "2") (pinfunction "K_2") (pintype "passive"))
      (node (ref "D233") (pin "2") (pinfunction "K_2") (pintype "passive"))
      (node (ref "D234") (pin "2") (pinfunction "K_2") (pintype "passive"))
      (node (ref "D235") (pin "2") (pinfunction "K_2") (pintype "passive"))
      (node (ref "D236") (pin "2") (pinfunction "K_2") (pintype "passive"))
      (node (ref "D237") (pin "2") (pinfunction "K_2") (pintype "passive"))
      (node (ref "D238") (pin "2") (pinfunction "K_2") (pintype "passive"))
      (node (ref "D239") (pin "2") (pinfunction "K_2") (pintype "passive"))
      (node (ref "D240") (pin "2") (pinfunction "K_2") (pintype "passive"))
      (node (ref "D241") (pin "2") (pinfunction "K_2") (pintype "passive"))
      (node (ref "D242") (pin "2") (pinfunction "K_2") (pintype "passive"))
    )
    (net (code "19") (name "/row4") (class "Default")
      (node (ref "D243") (pin "2") (pinfunction "K_2") (pintype "passive"))
      (node (ref "D244") (pin "2") (pinfunction "K_2") (pintype "passive"))
      (node (ref "D245") (pin "2") (pinfunction "K_2") (pintype "passive"))
      (node (ref "D246") (pin "2") (pinfunction "K_2") (pintype "passive"))
      (node (ref "D247") (pin "2") (pinfunction "K_2") (pintype "passive"))
      (node (ref "D248") (pin "2") (pinfunction "K_2") (pintype "passive"))
      (node (ref "D249") (pin "2") (pinfunction "K_2") (pintype "passive"))
      (node (ref "D250") (pin "2") (pinfunction "K_2") (pintype "passive"))
      (node (ref "D251") (pin "2") (pinfunction "K_2") (pintype "passive"))
      (node (ref "D252") (pin "2") (pinfunction "K_2") (pintype "passive"))
      (node (ref "D253") (pin "2") (pinfunction "K_2") (pintype "passive"))
      (node (ref "D254") (pin "2") (pinfunction "K_2") (pintype "passive"))
      (node (ref "D256") (pin "2") (pinfunction "K_2") (pintype "passive"))
      (node (ref "D269") (pin "2") (pinfunction "K_2") (pintype "passive"))
    )
    (net (code "20") (name "/row5") (class "Default")
      (node (ref "D257") (pin "2") (pinfunction "K_2") (pintype "passive"))
      (node (ref "D258") (pin "2") (pinfunction "K_2") (pintype "passive"))
      (node (ref "D260") (pin "2") (pinfunction "K_2") (pintype "passive"))
      (node (ref "D262") (pin "2") (pinfunction "K_2") (pintype "passive"))
      (node (ref "D264") (pin "2") (pinfunction "K_2") (pintype "passive"))
      (node (ref "D265") (pin "2") (pinfunction "K_2") (pintype "passive"))
      (node (ref "D266") (pin "2") (pinfunction "K_2") (pintype "passive"))
      (node (ref "D267") (pin "2") (pinfunction "K_2") (pintype "passive"))
      (node (ref "D268") (pin "2") (pinfunction "K_2") (pintype "passive"))
      (node (ref "D270") (pin "2") (pinfunction "K_2") (pintype "passive"))
    )
    (net (code "21") (name "Net-(D201-A)") (class "Default")
      (node (ref "D201") (pin "1") (pinfunction "A_1") (pintype "passive"))
      (node (ref "S201") (pin "1") (pinfunction "1_1") (pintype "passive"))
    )
    (net (code "22") (name "Net-(D202-A)") (class "Default")
      (node (ref "D202") (pin "1") (pinfunction "A_1") (pintype "passive"))
      (node (ref "S202") (pin "1") (pinfunction "1_1") (pintype "passive"))
    )
    (net (code "23") (name "Net-(D203-A)") (class "Default")
      (node (ref "D203") (pin "1") (pinfunction "A_1") (pintype "passive"))
      (node (ref "S203") (pin "1") (pinfunction "1_1") (pintype "passive"))
    )
    (net (code "24") (name "Net-(D204-A)") (class "Default")
      (node (ref "D204") (pin "1") (pinfunction "A_1") (pintype "passive"))
      (node (ref "S204") (pin "1") (pinfunction "1_1") (pintype "passive"))
    )
    (net (code "25") (name "Net-(D205-A)") (class "Default")
      (node (ref "D205") (pin "1") (pinfunction "A_1") (pintype "passive"))
      (node (ref "S205") (pin "1") (pinfunction "1_1") (pintype "passive"))
    )
    (net (code "26") (name "Net-(D206-A)") (class "Default")
      (node (ref "D206") (pin "1") (pinfunction "A_1") (pintype "passive"))
      (node (ref "S206") (pin "1") (pinfunction "1_1") (pintype "passive"))
    )
    (net (code "27") (name "Net-(D207-A)") (class "Default")
      (node (ref "D207") (pin "1") (pinfunction "A_1") (pintype "passive"))
      (node (ref "S207") (pin "1") (pinfunction "1_1") (pintype "passive"))
    )
    (net (code "28") (name "Net-(D208-A)") (class "Default")
      (node (ref "D208") (pin "1") (pinfunction "A_1") (pintype "passive"))
      (node (ref "S208") (pin "1") (pinfunction "1_1") (pintype "passive"))
    )
    (net (code "29") (name "Net-(D209-A)") (class "Default")
      (node (ref "D209") (pin "1") (pinfunction "A_1") (pintype "passive"))
      (node (ref "S209") (pin "1") (pinfunction "1_1") (pintype "passive"))
    )
    (net (code "30") (name "Net-(D210-A)") (class "Default")
      (node (ref "D210") (pin "1") (pinfunction "A_1") (pintype "passive"))
      (node (ref "S210") (pin "1") (pinfunction "1_1") (pintype "passive"))
    )
    (net (code "31") (name "Net-(D211-A)") (class "Default")
      (node (ref "D211") (pin "1") (pinfunction "A_1") (pintype "passive"))
      (node (ref "S211") (pin "1") (pinfunction "1_1") (pintype "passive"))
    )
    (net (code "32") (name "Net-(D212-A)") (class "Default")
      (node (ref "D212") (pin "1") (pinfunction "A_1") (pintype "passive"))
      (node (ref "S212") (pin "1") (pinfunction "1_1") (pintype "passive"))
    )
    (net (code "33") (name "Net-(D213-A)") (class "Default")
      (node (ref "D213") (pin "1") (pinfunction "A_1") (pintype "passive"))
      (node (ref "S213") (pin "1") (pinfunction "1_1") (pintype "passive"))
    )
    (net (code "34") (name "Net-(D214-A)") (class "Default")
      (node (ref "D214") (pin "1") (pinfunction "A_1") (pintype "passive"))
      (node (ref "S214") (pin "1") (pinfunction "1_1") (pintype "passive"))
    )
    (net (code "35") (name "Net-(D215-A)") (class "Default")
      (node (ref "D215") (pin "1") (pinfunction "A_1") (pintype "passive"))
      (node (ref "S215") (pin "1") (pinfunction "1_1") (pintype "passive"))
    )
    (net (code "36") (name "Net-(D216-A)") (class "Default")
      (node (ref "D216") (pin "1") (pinfunction "A_1") (pintype "passive"))
      (node (ref "S216") (pin "1") (pinfunction "1_1") (pintype "passive"))
    )
    (net (code "37") (name "Net-(D217-A)") (class "Default")
      (node (ref "D217") (pin "1") (pinfunction "A_1") (pintype "passive"))
      (node (ref "S217") (pin "1") (pinfunction "1_1") (pintype "passive"))
    )
    (net (code "38") (name "Net-(D218-A)") (class "Default")
      (node (ref "D218") (pin "1") (pinfunction "A_1") (pintype "passive"))
      (node (ref "S218") (pin "1") (pinfunction "1_1") (pintype "passive"))
    )
    (net (code "39") (name "Net-(D219-A)") (class "Default")
      (node (ref "D219") (pin "1") (pinfunction "A_1") (pintype "passive"))
      (node (ref "S219") (pin "1") (pinfunction "1_1") (pintype "passive"))
    )
    (net (code "40") (name "Net-(D220-A)") (class "Default")
      (node (ref "D220") (pin "1") (pinfunction "A_1") (pintype "passive"))
      (node (ref "S220") (pin "1") (pinfunction "1_1") (pintype "passive"))
    )
    (net (code "41") (name "Net-(D221-A)") (class "Default")
      (node (ref "D221") (pin "1") (pinfunction "A_1") (pintype "passive"))
      (node (ref "S221") (pin "1") (pinfunction "1_1") (pintype "passive"))
    )
    (net (code "42") (name "Net-(D222-A)") (class "Default")
      (node (ref "D222") (pin "1") (pinfunction "A_1") (pintype "passive"))
      (node (ref "S222") (pin "1") (pinfunction "1_1") (pintype "passive"))
    )
    (net (code "43") (name "Net-(D223-A)") (class "Default")
      (node (ref "D223") (pin "1") (pinfunction "A_1") (pintype "passive"))
      (node (ref "S223") (pin "1") (pinfunction "1_1") (pintype "passive"))
    )
    (net (code "44") (name "Net-(D224-A)") (class "Default")
      (node (ref "D224") (pin "1") (pinfunction "A_1") (pintype "passive"))
      (node (ref "S224") (pin "1") (pinfunction "1_1") (pintype "passive"))
    )
    (net (code "45") (name "Net-(D225-A)") (class "Default")
      (node (ref "D225") (pin "1") (pinfunction "A_1") (pintype "passive"))
      (node (ref "S225") (pin "1") (pinfunction "1_1") (pintype "passive"))
    )
    (net (code "46") (name "Net-(D226-A)") (class "Default")
      (node (ref "D226") (pin "1") (pinfunction "A_1") (pintype "passive"))
      (node (ref "S226") (pin "1") (pinfunction "1_1") (pintype "passive"))
    )
    (net (code "47") (name "Net-(D227-A)") (class "Default")
      (node (ref "D227") (pin "1") (pinfunction "A_1") (pintype "passive"))
      (node (ref "S227") (pin "1") (pinfunction "1_1") (pintype "passive"))
    )
    (net (code "48") (name "Net-(D228-A)") (class "Default")
      (node (ref "D228") (pin "1") (pinfunction "A_1") (pintype "passive"))
      (node (ref "S228") (pin "1") (pinfunction "1_1") (pintype "passive"))
    )
    (net (code "49") (name "Net-(D229-A)") (class "Default")
      (node (ref "D229") (pin "1") (pinfunction "A_1") (pintype "passive"))
      (node (ref "S229") (pin "1") (pinfunction "1_1") (pintype "passive"))
    )
    (net (code "50") (name "Net-(D230-A)") (class "Default")
      (node (ref "D230") (pin "1") (pinfunction "A_1") (pintype "passive"))
      (node (ref "S230") (pin "1") (pinfunction "1_1") (pintype "passive"))
    )
    (net (code "51") (name "Net-(D231-A)") (class "Default")
      (node (ref "D231") (pin "1") (pinfunction "A_1") (pintype "passive"))
      (node (ref "S231") (pin "1") (pinfunction "1_1") (pintype "passive"))
    )
    (net (code "52") (name "Net-(D232-A)") (class "Default")
      (node (ref "D232") (pin "1") (pinfunction "A_1") (pintype "passive"))
      (node (ref "S232") (pin "1") (pinfunction "1_1") (pintype "passive"))
    )
    (net (code "53") (name "Net-(D233-A)") (class "Default")
      (node (ref "D233") (pin "1") (pinfunction "A_1") (pintype "passive"))
      (node (ref "S233") (pin "1") (pinfunction "1_1") (pintype "passive"))
    )
    (net (code "54") (name "Net-(D234-A)") (class "Default")
      (node (ref "D234") (pin "1") (pinfunction "A_1") (pintype "passive"))
      (node (ref "S234") (pin "1") (pinfunction "1_1") (pintype "passive"))
    )
    (net (code "55") (name "Net-(D235-A)") (class "Default")
      (node (ref "D235") (pin "1") (pinfunction "A_1") (pintype "passive"))
      (node (ref "S235") (pin "1") (pinfunction "1_1") (pintype "passive"))
    )
    (net (code "56") (name "Net-(D236-A)") (class "Default")
      (node (ref "D236") (pin "1") (pinfunction "A_1") (pintype "passive"))
      (node (ref "S236") (pin "1") (pinfunction "1_1") (pintype "passive"))
    )
    (net (code "57") (name "Net-(D237-A)") (class "Default")
      (node (ref "D237") (pin "1") (pinfunction "A_1") (pintype "passive"))
      (node (ref "S237") (pin "1") (pinfunction "1_1") (pintype "passive"))
    )
    (net (code "58") (name "Net-(D238-A)") (class "Default")
      (node (ref "D238") (pin "1") (pinfunction "A_1") (pintype "passive"))
      (node (ref "S238") (pin "1") (pinfunction "1_1") (pintype "passive"))
    )
    (net (code "59") (name "Net-(D239-A)") (class "Default")
      (node (ref "D239") (pin "1") (pinfunction "A_1") (pintype "passive"))
      (node (ref "S239") (pin "1") (pinfunction "1_1") (pintype "passive"))
    )
    (net (code "60") (name "Net-(D240-A)") (class "Default")
      (node (ref "D240") (pin "1") (pinfunction "A_1") (pintype "passive"))
      (node (ref "S240") (pin "1") (pinfunction "1_1") (pintype "passive"))
    )
    (net (code "61") (name "Net-(D241-A)") (class "Default")
      (node (ref "D241") (pin "1") (pinfunction "A_1") (pintype "passive"))
      (node (ref "S241") (pin "1") (pinfunction "1_1") (pintype "passive"))
    )
    (net (code "62") (name "Net-(D242-A)") (class "Default")
      (node (ref "D242") (pin "1") (pinfunction "A_1") (pintype "passive"))
      (node (ref "S242") (pin "1") (pinfunction "1_1") (pintype "passive"))
    )
    (net (code "63") (name "Net-(D243-A)") (class "Default")
      (node (ref "D243") (pin "1") (pinfunction "A_1") (pintype "passive"))
      (node (ref "S243") (pin "1") (pinfunction "1_1") (pintype "passive"))
    )
    (net (code "64") (name "Net-(D244-A)") (class "Default")
      (node (ref "D244") (pin "1") (pinfunction "A_1") (pintype "passive"))
      (node (ref "S244") (pin "1") (pinfunction "1_1") (pintype "passive"))
    )
    (net (code "65") (name "Net-(D245-A)") (class "Default")
      (node (ref "D245") (pin "1") (pinfunction "A_1") (pintype "passive"))
      (node (ref "S245") (pin "1") (pinfunction "1_1") (pintype "passive"))
    )
    (net (code "66") (name "Net-(D246-A)") (class "Default")
      (node (ref "D246") (pin "1") (pinfunction "A_1") (pintype "passive"))
      (node (ref "S246") (pin "1") (pinfunction "1_1") (pintype "passive"))
    )
    (net (code "67") (name "Net-(D247-A)") (class "Default")
      (node (ref "D247") (pin "1") (pinfunction "A_1") (pintype "passive"))
      (node (ref "S247") (pin "1") (pinfunction "1_1") (pintype "passive"))
    )
    (net (code "68") (name "Net-(D248-A)") (class "Default")
      (node (ref "D248") (pin "1") (pinfunction "A_1") (pintype "passive"))
      (node (ref "S248") (pin "1") (pinfunction "1_1") (pintype "passive"))
    )
    (net (code "69") (name "Net-(D249-A)") (class "Default")
      (node (ref "D249") (pin "1") (pinfunction "A_1") (pintype "passive"))
      (node (ref "S249") (pin "1") (pinfunction "1_1") (pintype "passive"))
    )
    (net (code "70") (name "Net-(D250-A)") (class "Default")
      (node (ref "D250") (pin "1") (pinfunction "A_1") (pintype "passive"))
      (node (ref "S250") (pin "1") (pinfunction "1_1") (pintype "passive"))
    )
    (net (code "71") (name "Net-(D251-A)") (class "Default")
      (node (ref "D251") (pin "1") (pinfunction "A_1") (pintype "passive"))
      (node (ref "S251") (pin "1") (pinfunction "1_1") (pintype "passive"))
    )
    (net (code "72") (name "Net-(D252-A)") (class "Default")
      (node (ref "D252") (pin "1") (pinfunction "A_1") (pintype "passive"))
      (node (ref "S252") (pin "1") (pinfunction "1_1") (pintype "passive"))
    )
    (net (code "73") (name "Net-(D253-A)") (class "Default")
      (node (ref "D253") (pin "1") (pinfunction "A_1") (pintype "passive"))
      (node (ref "S253") (pin "1") (pinfunction "1_1") (pintype "passive"))
    )
    (net (code "74") (name "Net-(D254-A)") (class "Default")
      (node (ref "D254") (pin "1") (pinfunction "A_1") (pintype "passive"))
      (node (ref "S254") (pin "1") (pinfunction "1_1") (pintype "passive"))
    )
    (net (code "75") (name "Net-(D256-A)") (class "Default")
      (node (ref "D256") (pin "1") (pinfunction "A_1") (pintype "passive"))
      (node (ref "S256") (pin "1") (pinfunction "1_1") (pintype "passive"))
    )
    (net (code "76") (name "Net-(D257-A)") (class "Default")
      (node (ref "D257") (pin "1") (pinfunction "A_1") (pintype "passive"))
      (node (ref "S257") (pin "2") (pinfunction "2_2") (pintype "passive"))
    )
    (net (code "77") (name "Net-(D258-A)") (class "Default")
      (node (ref "D258") (pin "1") (pinfunction "A_1") (pintype "passive"))
      (node (ref "S258") (pin "1") (pinfunction "1_1") (pintype "passive"))
    )
    (net (code "78") (name "Net-(D259-A)") (class "Default")
      (node (ref "D259") (pin "1") (pinfunction "A_1") (pintype "passive"))
      (node (ref "S259") (pin "1") (pinfunction "1_1") (pintype "passive"))
    )
    (net (code "79") (name "Net-(D260-A)") (class "Default")
      (node (ref "D260") (pin "1") (pinfunction "A_1") (pintype "passive"))
      (node (ref "S260") (pin "1") (pinfunction "1_1") (pintype "passive"))
    )
    (net (code "80") (name "Net-(D262-A)") (class "Default")
      (node (ref "D262") (pin "1") (pinfunction "A_1") (pintype "passive"))
      (node (ref "S262") (pin "1") (pinfunction "1_1") (pintype "passive"))
    )
    (net (code "81") (name "Net-(D264-A)") (class "Default")
      (node (ref "D264") (pin "1") (pinfunction "A_1") (pintype "passive"))
      (node (ref "S264") (pin "1") (pinfunction "1_1") (pintype "passive"))
    )
    (net (code "82") (name "Net-(D265-A)") (class "Default")
      (node (ref "D265") (pin "1") (pinfunction "A_1") (pintype "passive"))
      (node (ref "S265") (pin "2") (pinfunction "2_2") (pintype "passive"))
    )
    (net (code "83") (name "Net-(D266-A)") (class "Default")
      (node (ref "D266") (pin "1") (pinfunction "A_1") (pintype "passive"))
      (node (ref "S266") (pin "1") (pinfunction "1_1") (pintype "passive"))
    )
    (net (code "84") (name "Net-(D267-A)") (class "Default")
      (node (ref "D267") (pin "1") (pinfunction "A_1") (pintype "passive"))
      (node (ref "S267") (pin "1") (pinfunction "1_1") (pintype "passive"))
    )
    (net (code "85") (name "Net-(D268-A)") (class "Default")
      (node (ref "D268") (pin "1") (pinfunction "A_1") (pintype "passive"))
      (node (ref "S268") (pin "1") (pinfunction "1_1") (pintype "passive"))
    )
    (net (code "86") (name "Net-(D269-A)") (class "Default")
      (node (ref "D269") (pin "1") (pinfunction "A_1") (pintype "passive"))
      (node (ref "S269") (pin "1") (pinfunction "1_1") (pintype "passive"))
    )
    (net (code "87") (name "Net-(D270-A)") (class "Default")
      (node (ref "D270") (pin "1") (pinfunction "A_1") (pintype "passive"))
      (node (ref "S270") (pin "1") (pinfunction "1_1") (pintype "passive"))
    )
  )
)
